# Esquematico.net
KiCad netlist of a schematic drawn in EAGLE
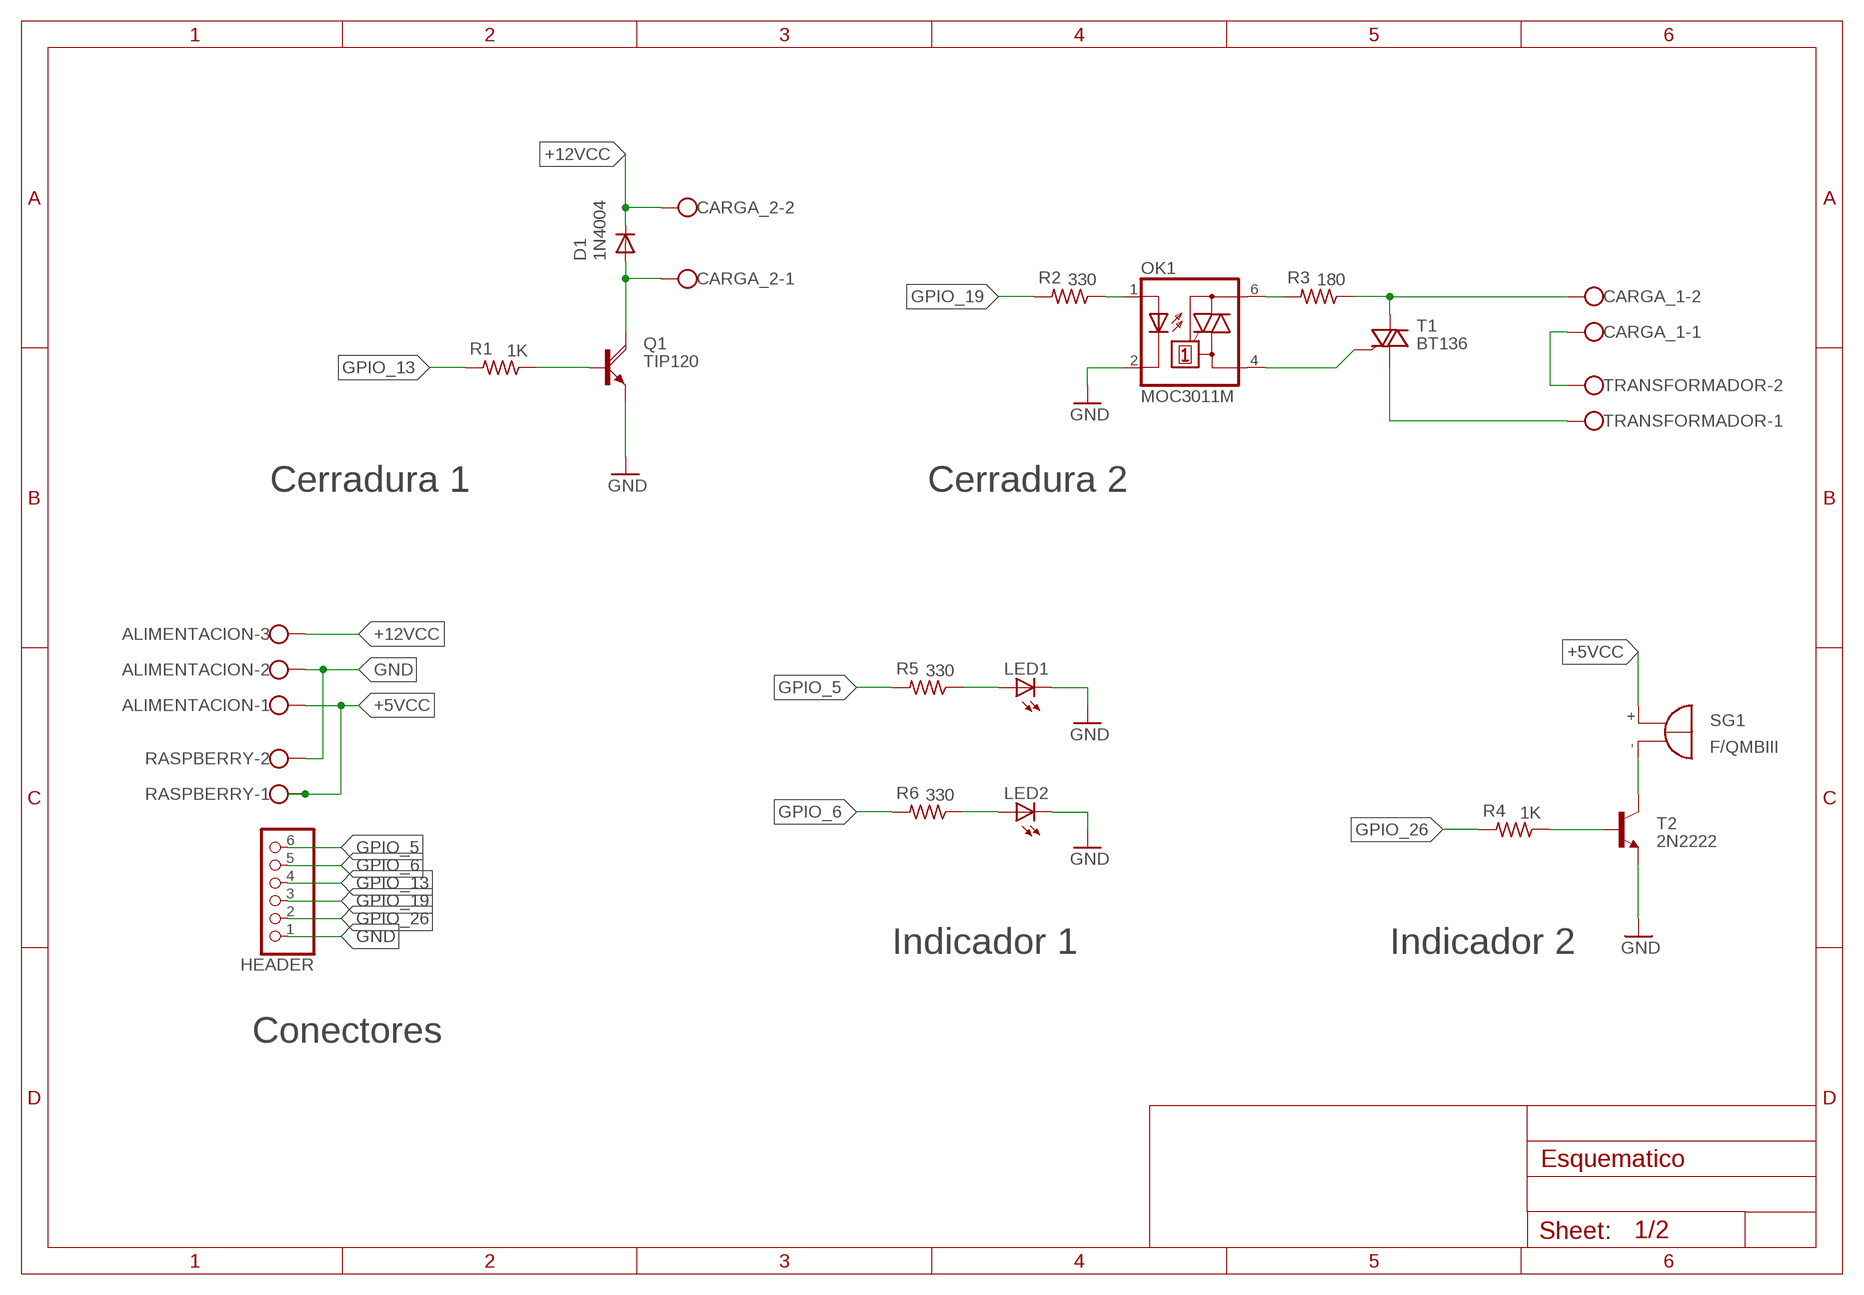
[diagram p0: schematic, sheet 1]
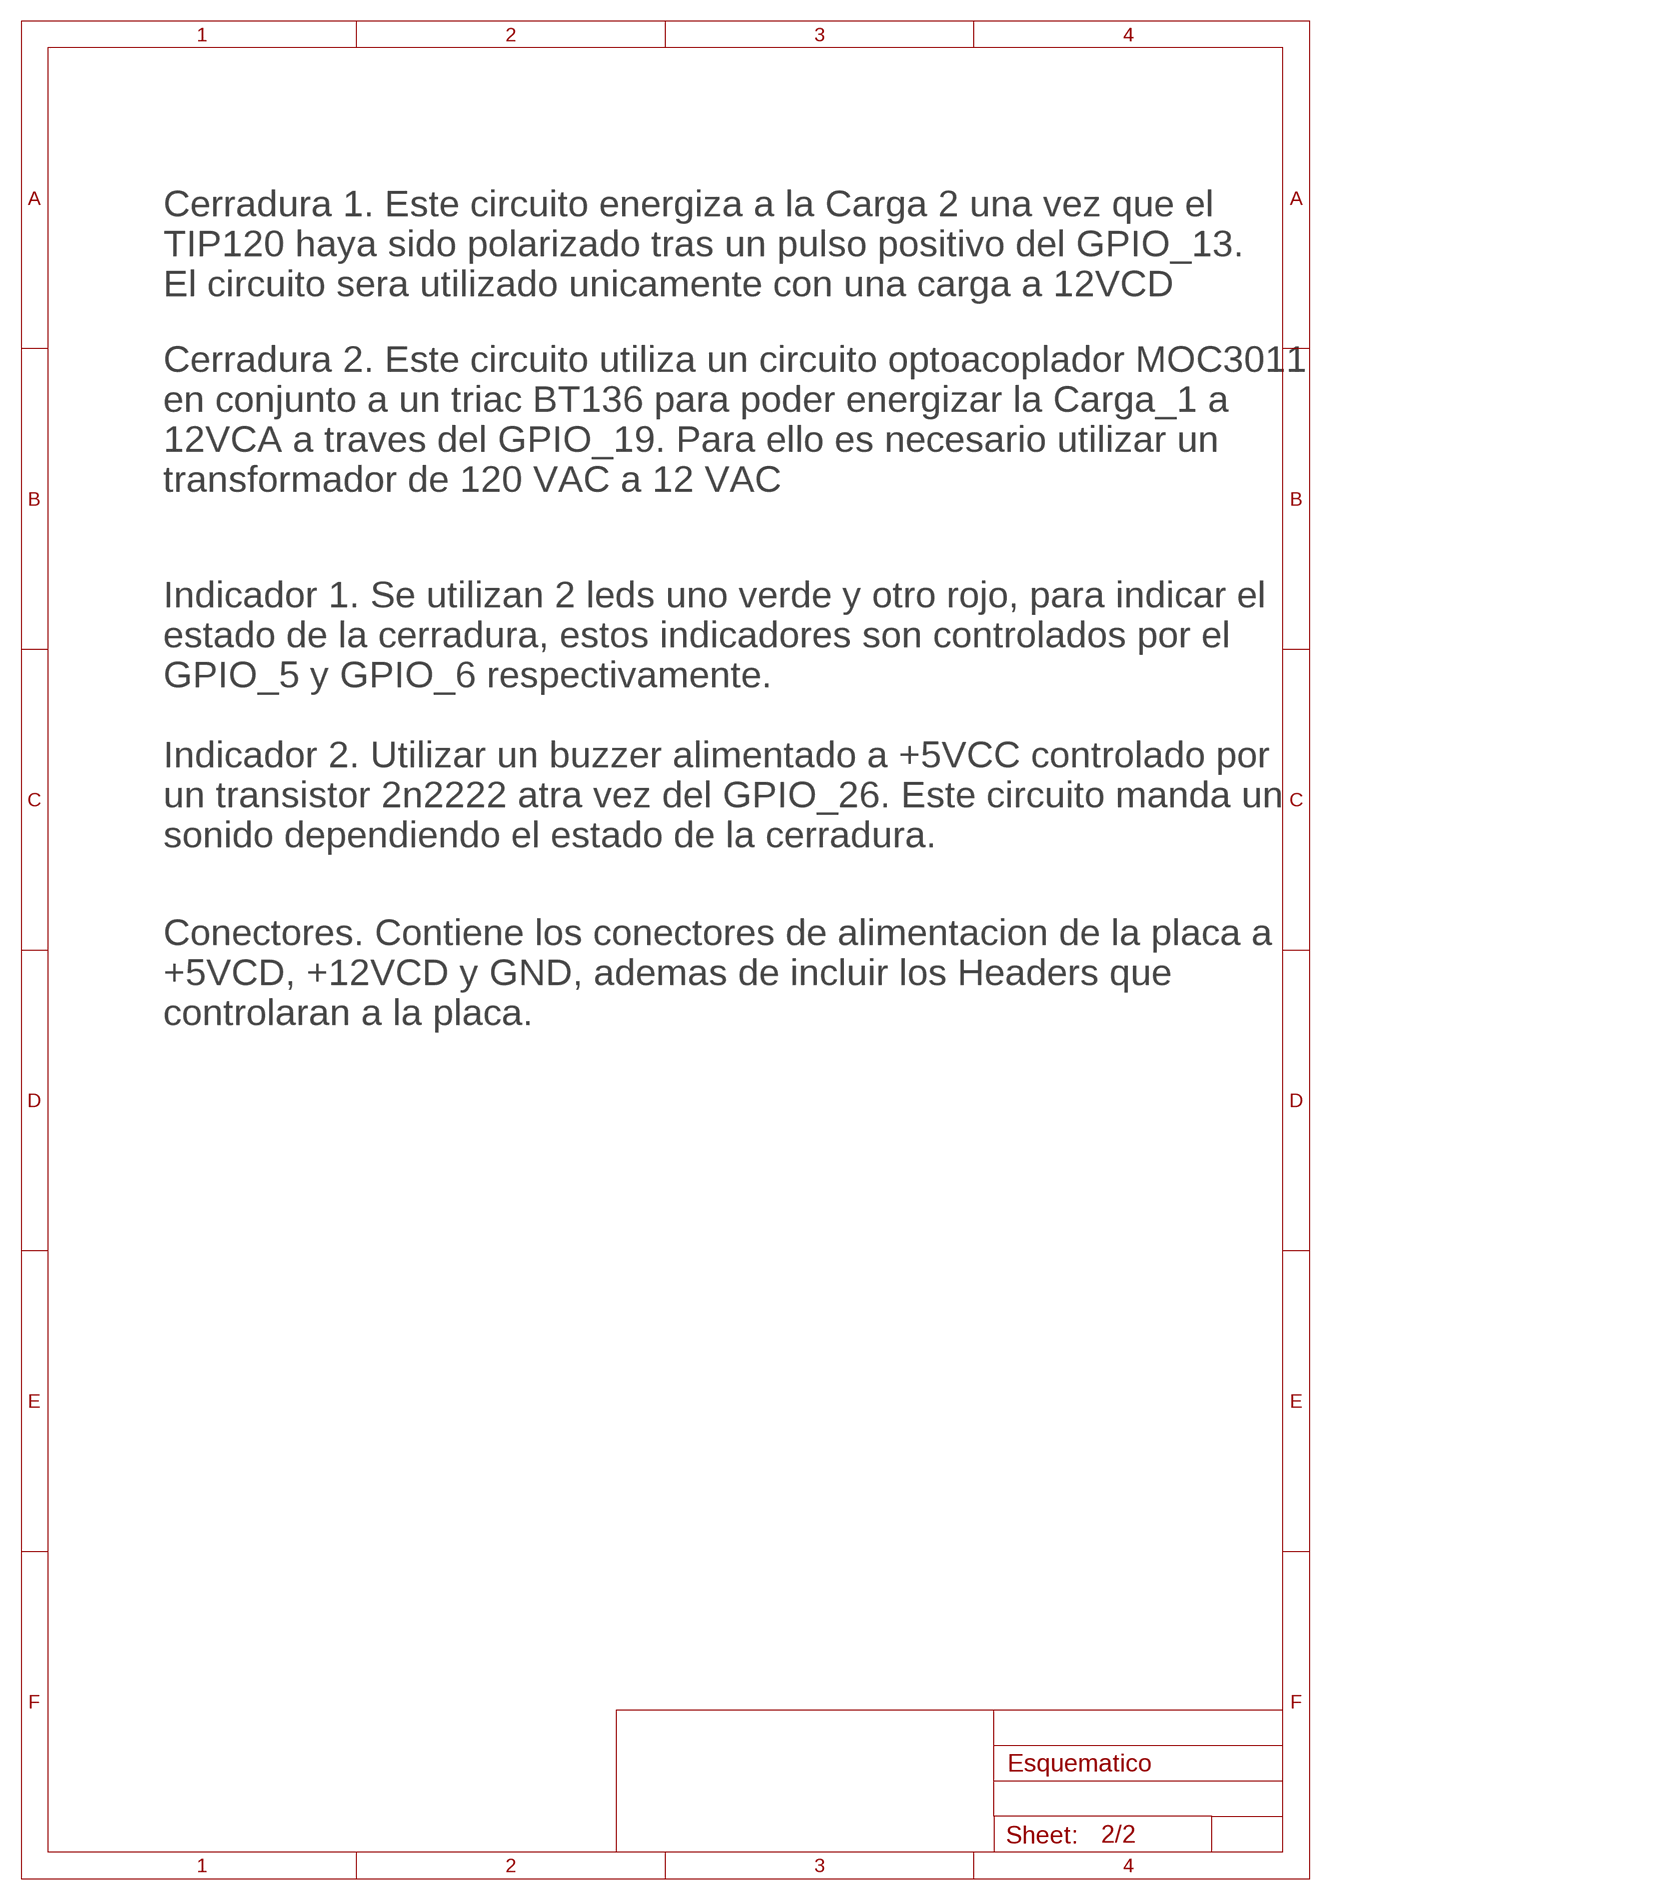
[diagram p1: schematic, sheet 2]

(export (version "E")
  (design (tool "Eeschema 10.0.6"))
  (components
    (comp (ref "ALIMENTACION")
      (value "W237-103")
      (footprint "eagle-import:W237-103")
      (fields (field (name "MPN") "237-103"))
      (libsource (lib "eagle-import") (part "W237-103"))
    )
    (comp (ref "CARGA_1")
      (value "W237-102")
      (footprint "eagle-import:W237-102")
      (fields (field (name "MPN") "237-102"))
      (libsource (lib "eagle-import") (part "W237-102"))
    )
    (comp (ref "CARGA_2")
      (value "W237-102")
      (footprint "eagle-import:W237-102")
      (fields (field (name "MPN") "237-102"))
      (libsource (lib "eagle-import") (part "W237-102"))
    )
    (comp (ref "D1")
      (value "1N4004")
      (footprint "eagle-import:DO41-10")
      (libsource (lib "eagle-import") (part "1N4004"))
    )
    (comp (ref "HEADER")
      (value "PINHD-1X6B")
      (footprint "eagle-import:1X06-BIG")
      (libsource (lib "eagle-import") (part "PINHD-1X6B"))
    )
    (comp (ref "LED1")
      (value "LED5MM")
      (footprint "eagle-import:LED5MM")
      (libsource (lib "eagle-import") (part "LED5MM"))
    )
    (comp (ref "LED2")
      (value "LED5MM")
      (footprint "eagle-import:LED5MM")
      (libsource (lib "eagle-import") (part "LED5MM"))
    )
    (comp (ref "OK1")
      (value "MOC3011M")
      (footprint "eagle-import:DIL06")
      (fields (field (name "MF") "FAIRCHILD SEMICONDUCTOR") (field (name "MPN") "MOC3011-M"))
      (libsource (lib "eagle-import") (part "MOC30M11"))
    )
    (comp (ref "Q1")
      (value "TIP120")
      (footprint "eagle-import:TO220AH")
      (libsource (lib "eagle-import") (part "TIP120"))
    )
    (comp (ref "R1")
      (value "1K")
      (footprint "eagle-import:0207_10")
      (libsource (lib "eagle-import") (part "R-US_0207/10"))
    )
    (comp (ref "R2")
      (value "330")
      (footprint "eagle-import:0207_10")
      (libsource (lib "eagle-import") (part "R-US_0207/10"))
    )
    (comp (ref "R3")
      (value "180")
      (footprint "eagle-import:0207_10")
      (libsource (lib "eagle-import") (part "R-US_0207/10"))
    )
    (comp (ref "R4")
      (value "1K")
      (footprint "eagle-import:0207_10")
      (libsource (lib "eagle-import") (part "R-US_0207/10"))
    )
    (comp (ref "R5")
      (value "330")
      (footprint "eagle-import:0207_10")
      (libsource (lib "eagle-import") (part "R-US_0207/10"))
    )
    (comp (ref "R6")
      (value "330")
      (footprint "eagle-import:0207_10")
      (libsource (lib "eagle-import") (part "R-US_0207/10"))
    )
    (comp (ref "RASPBERRY")
      (value "W237-102")
      (footprint "eagle-import:W237-102")
      (fields (field (name "MPN") "237-102"))
      (libsource (lib "eagle-import") (part "W237-102"))
    )
    (comp (ref "SG1")
      (value "F/QMBIII")
      (footprint "eagle-import:F_QMBIII")
      (libsource (lib "eagle-import") (part "F/QMBIII"))
    )
    (comp (ref "T1")
      (value "BT136")
      (footprint "eagle-import:TO220AB")
      (libsource (lib "eagle-import") (part "BT136"))
    )
    (comp (ref "T2")
      (value "2N2222")
      (footprint "eagle-import:TO92-EBC-OVAL")
      (libsource (lib "eagle-import") (part "2N2222"))
    )
    (comp (ref "TRANSFORMADOR")
      (value "W237-102")
      (footprint "eagle-import:W237-102")
      (fields (field (name "MPN") "237-102"))
      (libsource (lib "eagle-import") (part "W237-102"))
    )
  )
  (nets
    (net (code "1") (name "+5VCC") (class "Default")
      (node (ref "ALIMENTACION") (pin "1") (pinfunction "KL_1") (pintype "passive"))
      (node (ref "RASPBERRY") (pin "1") (pinfunction "KL_1") (pintype "passive"))
      (node (ref "SG1") (pin "+") (pinfunction "-_+") (pintype "passive"))
    )
    (net (code "2") (name "+12VCC") (class "Default")
      (node (ref "ALIMENTACION") (pin "3") (pinfunction "KL_3") (pintype "passive"))
      (node (ref "CARGA_2") (pin "2") (pinfunction "KL_2") (pintype "passive"))
      (node (ref "D1") (pin "C") (pinfunction "C_C") (pintype "passive"))
    )
    (net (code "3") (name "GND") (class "Default")
      (node (ref "ALIMENTACION") (pin "2") (pinfunction "KL_2") (pintype "passive"))
      (node (ref "HEADER") (pin "1") (pinfunction "1_1") (pintype "passive"))
      (node (ref "LED1") (pin "K") (pinfunction "C_K") (pintype "passive"))
      (node (ref "LED2") (pin "K") (pinfunction "C_K") (pintype "passive"))
      (node (ref "OK1") (pin "2") (pinfunction "C_2") (pintype "passive"))
      (node (ref "Q1") (pin "E") (pinfunction "E_E") (pintype "passive"))
      (node (ref "RASPBERRY") (pin "2") (pinfunction "KL_2") (pintype "passive"))
      (node (ref "T2") (pin "E") (pinfunction "E_E") (pintype "passive"))
    )
    (net (code "4") (name "GPIO_5") (class "Default")
      (node (ref "HEADER") (pin "6") (pinfunction "6_6") (pintype "passive"))
      (node (ref "R5") (pin "2") (pinfunction "2_2") (pintype "passive"))
    )
    (net (code "5") (name "GPIO_6") (class "Default")
      (node (ref "HEADER") (pin "5") (pinfunction "5_5") (pintype "passive"))
      (node (ref "R6") (pin "2") (pinfunction "2_2") (pintype "passive"))
    )
    (net (code "6") (name "GPIO_13") (class "Default")
      (node (ref "HEADER") (pin "4") (pinfunction "4_4") (pintype "passive"))
      (node (ref "R1") (pin "2") (pinfunction "2_2") (pintype "passive"))
    )
    (net (code "7") (name "GPIO_19") (class "Default")
      (node (ref "HEADER") (pin "3") (pinfunction "3_3") (pintype "passive"))
      (node (ref "R2") (pin "2") (pinfunction "2_2") (pintype "passive"))
    )
    (net (code "8") (name "GPIO_26") (class "Default")
      (node (ref "HEADER") (pin "2") (pinfunction "2_2") (pintype "passive"))
      (node (ref "R4") (pin "2") (pinfunction "2_2") (pintype "passive"))
    )
    (net (code "9") (name "Net-(CARGA_1A-KL)") (class "Default")
      (node (ref "CARGA_1") (pin "1") (pinfunction "KL_1") (pintype "passive"))
      (node (ref "TRANSFORMADOR") (pin "2") (pinfunction "KL_2") (pintype "passive"))
    )
    (net (code "10") (name "Net-(CARGA_1B-KL)") (class "Default")
      (node (ref "CARGA_1") (pin "2") (pinfunction "KL_2") (pintype "passive"))
      (node (ref "R3") (pin "1") (pinfunction "1_1") (pintype "passive"))
      (node (ref "T1") (pin "2") (pinfunction "A2_2") (pintype "passive"))
    )
    (net (code "11") (name "Net-(CARGA_2A-KL)") (class "Default")
      (node (ref "CARGA_2") (pin "1") (pinfunction "KL_1") (pintype "passive"))
      (node (ref "D1") (pin "A") (pinfunction "A_A") (pintype "passive"))
      (node (ref "Q1") (pin "C") (pinfunction "C_C") (pintype "passive"))
    )
    (net (code "12") (name "Net-(LED1-PadA)") (class "Default")
      (node (ref "LED1") (pin "A") (pinfunction "A_A") (pintype "passive"))
      (node (ref "R5") (pin "1") (pinfunction "1_1") (pintype "passive"))
    )
    (net (code "13") (name "Net-(LED2-PadA)") (class "Default")
      (node (ref "LED2") (pin "A") (pinfunction "A_A") (pintype "passive"))
      (node (ref "R6") (pin "1") (pinfunction "1_1") (pintype "passive"))
    )
    (net (code "14") (name "Net-(OK1-A)") (class "Default")
      (node (ref "OK1") (pin "1") (pinfunction "A_1") (pintype "passive"))
      (node (ref "R2") (pin "1") (pinfunction "1_1") (pintype "passive"))
    )
    (net (code "15") (name "Net-(OK1-A1)") (class "Default")
      (node (ref "OK1") (pin "4") (pinfunction "A1_4") (pintype "passive"))
      (node (ref "T1") (pin "3") (pinfunction "G_3") (pintype "passive"))
    )
    (net (code "16") (name "Net-(OK1-A2)") (class "Default")
      (node (ref "OK1") (pin "6") (pinfunction "A2_6") (pintype "passive"))
      (node (ref "R3") (pin "2") (pinfunction "2_2") (pintype "passive"))
    )
    (net (code "17") (name "Net-(Q1-PadB)") (class "Default")
      (node (ref "Q1") (pin "B") (pinfunction "B_B") (pintype "passive"))
      (node (ref "R1") (pin "1") (pinfunction "1_1") (pintype "passive"))
    )
    (net (code "18") (name "Net-(R4-Pad1)") (class "Default")
      (node (ref "R4") (pin "1") (pinfunction "1_1") (pintype "passive"))
      (node (ref "T2") (pin "B") (pinfunction "B_B") (pintype "passive"))
    )
    (net (code "19") (name "Net-(SG1-+)") (class "Default")
      (node (ref "SG1") (pin "-") (pinfunction "+_-") (pintype "passive"))
      (node (ref "T2") (pin "C") (pinfunction "C_C") (pintype "passive"))
    )
    (net (code "20") (name "Net-(T1-A1)") (class "Default")
      (node (ref "T1") (pin "1") (pinfunction "A1_1") (pintype "passive"))
      (node (ref "TRANSFORMADOR") (pin "1") (pinfunction "KL_1") (pintype "passive"))
    )
  )
)
